# schema_v3_1.net
KiCad netlist of a schematic drawn in EAGLE
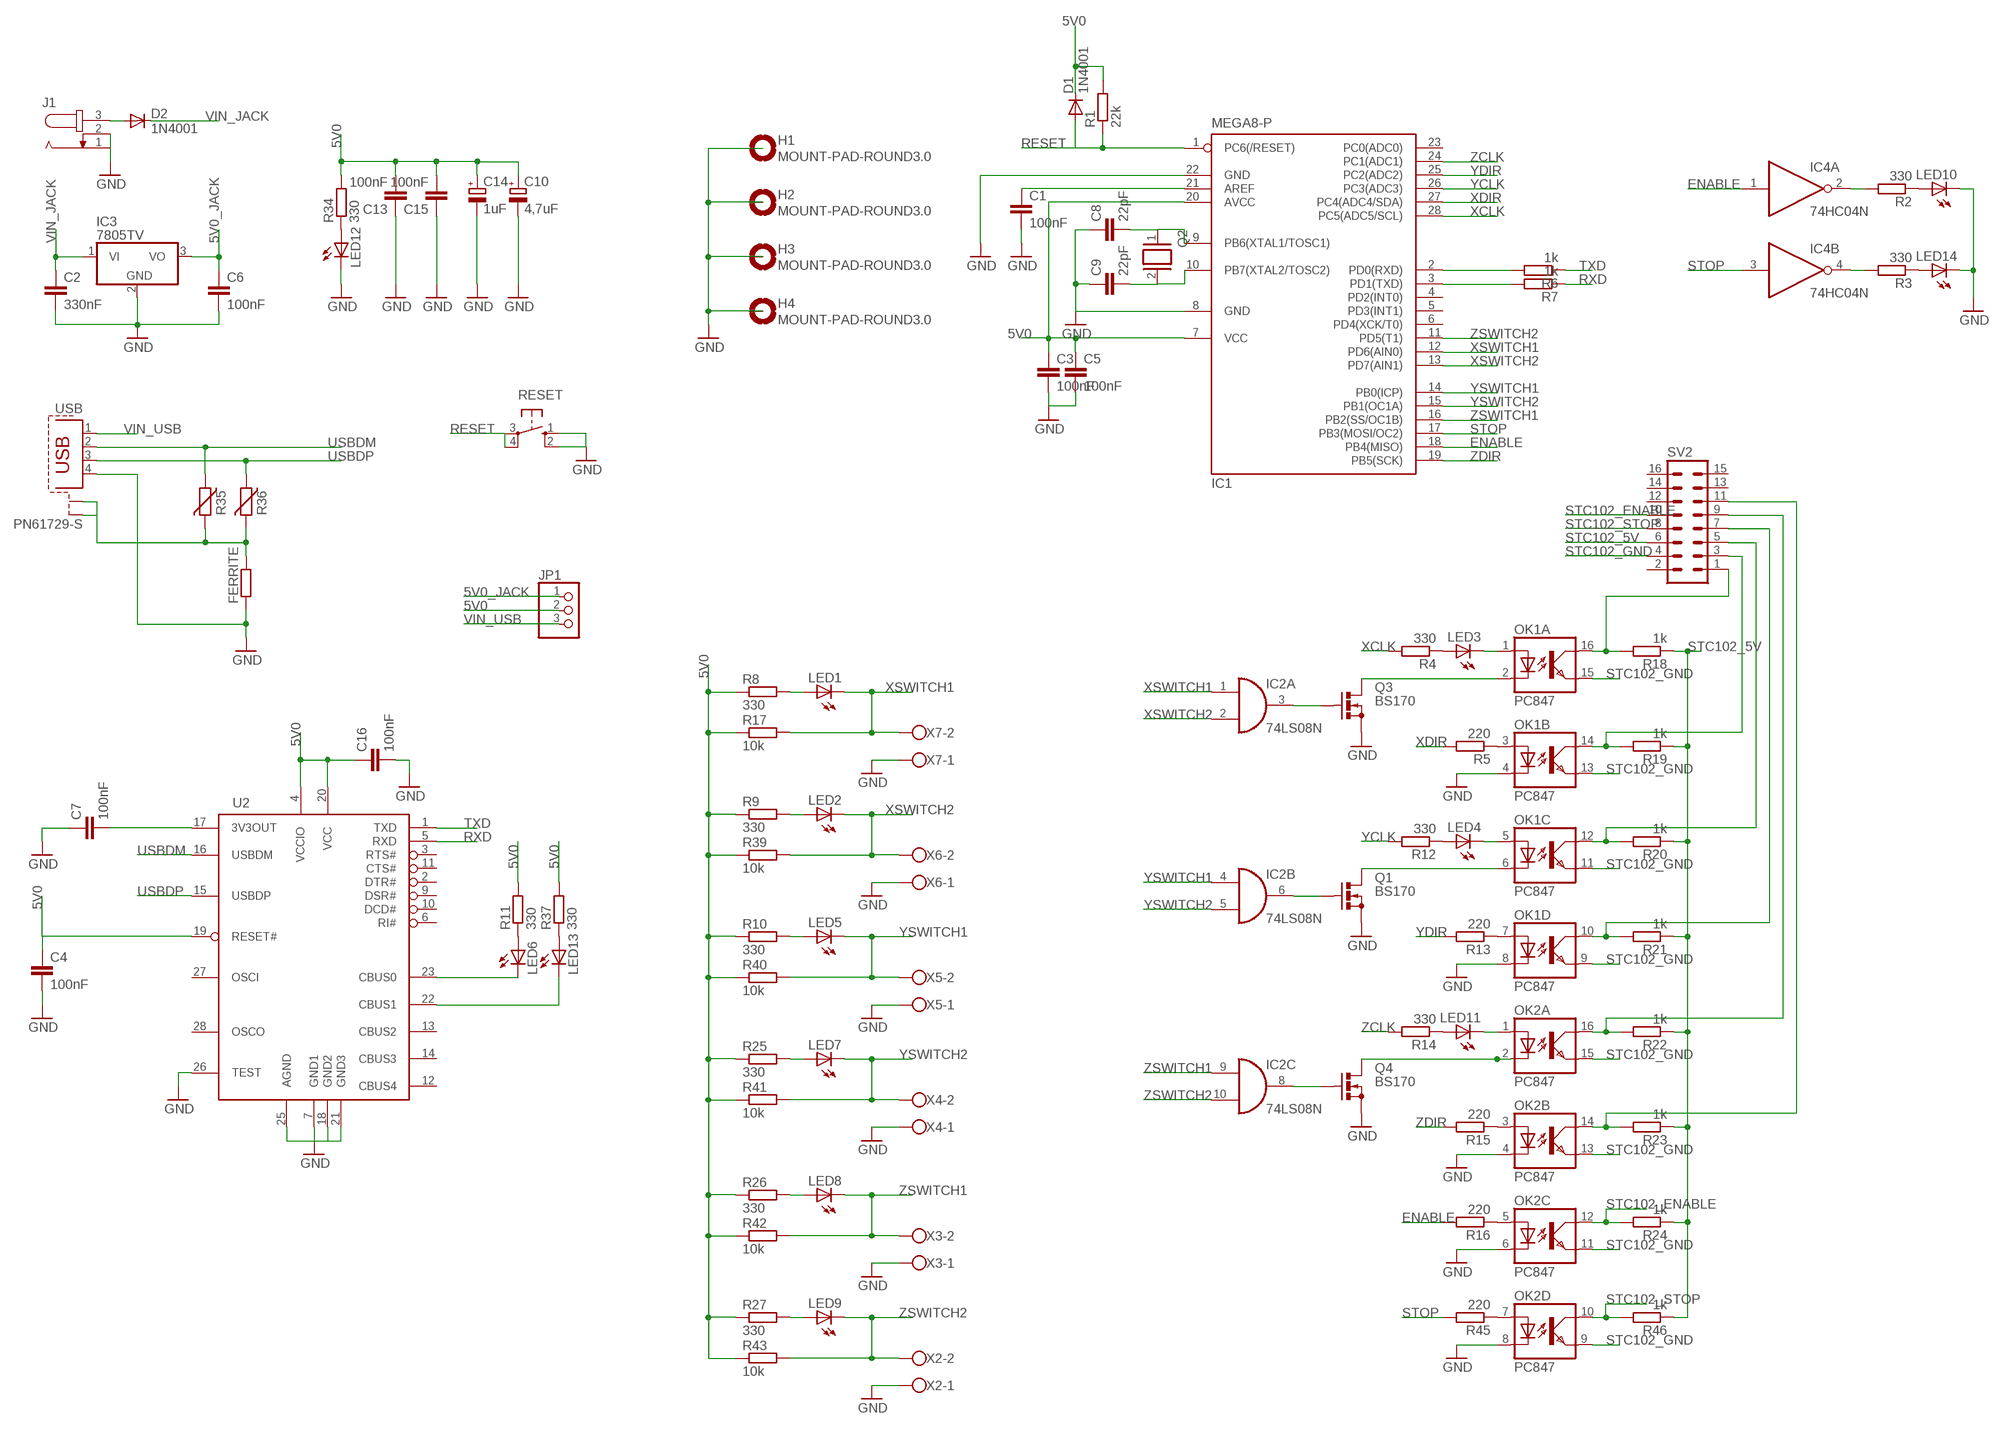
[diagram p0: schematic, sheet 1]

(export (version "E")
  (design (tool "Eeschema 10.0.6"))
  (components
    (comp (ref "C1")
      (value "100nF")
      (footprint "eagle-import:C0805")
      (libsource (lib "eagle-import") (part "C-EUC0805"))
    )
    (comp (ref "C2")
      (value "330nF")
      (footprint "eagle-import:C025-025X050")
      (libsource (lib "eagle-import") (part "C-EU025-025X050"))
    )
    (comp (ref "C3")
      (value "100nF")
      (footprint "eagle-import:C025-025X050")
      (libsource (lib "eagle-import") (part "C-EU025-025X050"))
    )
    (comp (ref "C4")
      (value "100nF")
      (footprint "eagle-import:C0603K")
      (libsource (lib "eagle-import") (part "C-EUC0603K"))
    )
    (comp (ref "C5")
      (value "100nF")
      (footprint "eagle-import:C025-025X050")
      (libsource (lib "eagle-import") (part "C-EU025-025X050"))
    )
    (comp (ref "C6")
      (value "100nF")
      (footprint "eagle-import:C025-025X050")
      (libsource (lib "eagle-import") (part "C-EU025-025X050"))
    )
    (comp (ref "C7")
      (value "100nF")
      (footprint "eagle-import:C0603K")
      (libsource (lib "eagle-import") (part "C-EUC0603K"))
    )
    (comp (ref "C8")
      (value "22pF")
      (footprint "eagle-import:C025-025X050")
      (libsource (lib "eagle-import") (part "C-EU025-025X050"))
    )
    (comp (ref "C9")
      (value "22pF")
      (footprint "eagle-import:C025-025X050")
      (libsource (lib "eagle-import") (part "C-EU025-025X050"))
    )
    (comp (ref "C10")
      (value "4,7uF")
      (footprint "eagle-import:E2,5-5")
      (libsource (lib "eagle-import") (part "CPOL-EUE2.5-5"))
    )
    (comp (ref "C13")
      (value "100nF")
      (footprint "eagle-import:C025-025X050")
      (libsource (lib "eagle-import") (part "C-EU025-025X050"))
    )
    (comp (ref "C14")
      (value "1uF")
      (footprint "eagle-import:E2,5-5")
      (libsource (lib "eagle-import") (part "CPOL-EUE2.5-5"))
    )
    (comp (ref "C15")
      (value "100nF")
      (footprint "eagle-import:C025-025X050")
      (libsource (lib "eagle-import") (part "C-EU025-025X050"))
    )
    (comp (ref "C16")
      (value "100nF")
      (footprint "eagle-import:C0603K")
      (libsource (lib "eagle-import") (part "C-EUC0603K"))
    )
    (comp (ref "D1")
      (value "1N4001")
      (footprint "eagle-import:DO41-10")
      (libsource (lib "eagle-import") (part "1N4004"))
    )
    (comp (ref "D2")
      (value "1N4001")
      (footprint "eagle-import:DO41-10")
      (libsource (lib "eagle-import") (part "1N4004"))
    )
    (comp (ref "FERRITE")
      (value "R-EU_M0805")
      (footprint "eagle-import:M0805")
      (libsource (lib "eagle-import") (part "resistor_R-EU_M0805"))
    )
    (comp (ref "H1")
      (value "MOUNT-PAD-ROUND3.0")
      (footprint "eagle-import:3,0-PAD")
      (libsource (lib "eagle-import") (part "MOUNT-PAD-ROUND3.0"))
    )
    (comp (ref "H2")
      (value "MOUNT-PAD-ROUND3.0")
      (footprint "eagle-import:3,0-PAD")
      (libsource (lib "eagle-import") (part "MOUNT-PAD-ROUND3.0"))
    )
    (comp (ref "H3")
      (value "MOUNT-PAD-ROUND3.0")
      (footprint "eagle-import:3,0-PAD")
      (libsource (lib "eagle-import") (part "MOUNT-PAD-ROUND3.0"))
    )
    (comp (ref "H4")
      (value "MOUNT-PAD-ROUND3.0")
      (footprint "eagle-import:3,0-PAD")
      (libsource (lib "eagle-import") (part "MOUNT-PAD-ROUND3.0"))
    )
    (comp (ref "IC1")
      (value "MEGA8-P")
      (footprint "eagle-import:DIL28-3")
      (libsource (lib "eagle-import") (part "MEGA8-P"))
    )
    (comp (ref "IC2")
      (value "74LS08N")
      (footprint "eagle-import:DIL14")
      (libsource (lib "eagle-import") (part "7408NLS"))
    )
    (comp (ref "IC3")
      (value "7805TV")
      (footprint "eagle-import:TO220V")
      (libsource (lib "eagle-import") (part "78TV05"))
    )
    (comp (ref "IC4")
      (value "74HC04N")
      (footprint "eagle-import:DIL14")
      (libsource (lib "eagle-import") (part "7404NHC"))
    )
    (comp (ref "J1")
      (value "JACK-PLUG0")
      (footprint "eagle-import:SPC4077")
      (libsource (lib "eagle-import") (part "JACK-PLUG0"))
    )
    (comp (ref "JP1")
      (value "PINHD-1X3")
      (footprint "eagle-import:1X03")
      (libsource (lib "eagle-import") (part "PINHD-1X3"))
    )
    (comp (ref "LED1")
      (value "LED3MM")
      (footprint "eagle-import:LED3MM")
      (libsource (lib "eagle-import") (part "LED3MM"))
    )
    (comp (ref "LED2")
      (value "LED3MM")
      (footprint "eagle-import:LED3MM")
      (libsource (lib "eagle-import") (part "LED3MM"))
    )
    (comp (ref "LED3")
      (value "LED3MM")
      (footprint "eagle-import:LED3MM")
      (libsource (lib "eagle-import") (part "LED3MM"))
    )
    (comp (ref "LED4")
      (value "LED3MM")
      (footprint "eagle-import:LED3MM")
      (libsource (lib "eagle-import") (part "LED3MM"))
    )
    (comp (ref "LED5")
      (value "LED3MM")
      (footprint "eagle-import:LED3MM")
      (libsource (lib "eagle-import") (part "LED3MM"))
    )
    (comp (ref "LED6")
      (value "LED3MM")
      (footprint "eagle-import:LED3MM")
      (libsource (lib "eagle-import") (part "LED3MM"))
    )
    (comp (ref "LED7")
      (value "LED3MM")
      (footprint "eagle-import:LED3MM")
      (libsource (lib "eagle-import") (part "LED3MM"))
    )
    (comp (ref "LED8")
      (value "LED3MM")
      (footprint "eagle-import:LED3MM")
      (libsource (lib "eagle-import") (part "LED3MM"))
    )
    (comp (ref "LED9")
      (value "LED3MM")
      (footprint "eagle-import:LED3MM")
      (libsource (lib "eagle-import") (part "LED3MM"))
    )
    (comp (ref "LED10")
      (value "LED3MM")
      (footprint "eagle-import:LED3MM")
      (libsource (lib "eagle-import") (part "LED3MM"))
    )
    (comp (ref "LED11")
      (value "LED3MM")
      (footprint "eagle-import:LED3MM")
      (libsource (lib "eagle-import") (part "LED3MM"))
    )
    (comp (ref "LED12")
      (value "LED3MM")
      (footprint "eagle-import:LED3MM")
      (libsource (lib "eagle-import") (part "LED3MM"))
    )
    (comp (ref "LED13")
      (value "LED3MM")
      (footprint "eagle-import:LED3MM")
      (libsource (lib "eagle-import") (part "LED3MM"))
    )
    (comp (ref "LED14")
      (value "LED3MM")
      (footprint "eagle-import:LED3MM")
      (libsource (lib "eagle-import") (part "LED3MM"))
    )
    (comp (ref "OK1")
      (value "PC847")
      (footprint "eagle-import:DIL16")
      (libsource (lib "eagle-import") (part "PC847"))
    )
    (comp (ref "OK2")
      (value "PC847")
      (footprint "eagle-import:DIL16")
      (libsource (lib "eagle-import") (part "PC847"))
    )
    (comp (ref "Q1")
      (value "BS170")
      (footprint "eagle-import:SOT54E")
      (libsource (lib "eagle-import") (part "BS170"))
    )
    (comp (ref "Q2")
      (value "XTAL/S")
      (footprint "eagle-import:QS")
      (libsource (lib "eagle-import") (part "XTAL/S"))
    )
    (comp (ref "Q3")
      (value "BS170")
      (footprint "eagle-import:SOT54E")
      (libsource (lib "eagle-import") (part "BS170"))
    )
    (comp (ref "Q4")
      (value "BS170")
      (footprint "eagle-import:SOT54E")
      (libsource (lib "eagle-import") (part "BS170"))
    )
    (comp (ref "R1")
      (value "22k")
      (footprint "eagle-import:0207_10")
      (libsource (lib "eagle-import") (part "R-EU_0207/10"))
    )
    (comp (ref "R2")
      (value "330")
      (footprint "eagle-import:0207_10")
      (libsource (lib "eagle-import") (part "R-EU_0207/10"))
    )
    (comp (ref "R3")
      (value "330")
      (footprint "eagle-import:0207_10")
      (libsource (lib "eagle-import") (part "R-EU_0207/10"))
    )
    (comp (ref "R4")
      (value "330")
      (footprint "eagle-import:0207_10")
      (libsource (lib "eagle-import") (part "R-EU_0207/10"))
    )
    (comp (ref "R5")
      (value "220")
      (footprint "eagle-import:0207_10")
      (libsource (lib "eagle-import") (part "R-EU_0207/10"))
    )
    (comp (ref "R6")
      (value "1k")
      (footprint "eagle-import:0207_10")
      (libsource (lib "eagle-import") (part "R-EU_0207/10"))
    )
    (comp (ref "R7")
      (value "1k")
      (footprint "eagle-import:0207_10")
      (libsource (lib "eagle-import") (part "R-EU_0207/10"))
    )
    (comp (ref "R8")
      (value "330")
      (footprint "eagle-import:0207_10")
      (libsource (lib "eagle-import") (part "R-EU_0207/10"))
    )
    (comp (ref "R9")
      (value "330")
      (footprint "eagle-import:0207_10")
      (libsource (lib "eagle-import") (part "R-EU_0207/10"))
    )
    (comp (ref "R10")
      (value "330")
      (footprint "eagle-import:0207_10")
      (libsource (lib "eagle-import") (part "R-EU_0207/10"))
    )
    (comp (ref "R11")
      (value "330")
      (footprint "eagle-import:0207_10")
      (libsource (lib "eagle-import") (part "R-EU_0207/10"))
    )
    (comp (ref "R12")
      (value "330")
      (footprint "eagle-import:0207_10")
      (libsource (lib "eagle-import") (part "R-EU_0207/10"))
    )
    (comp (ref "R13")
      (value "220")
      (footprint "eagle-import:0207_10")
      (libsource (lib "eagle-import") (part "R-EU_0207/10"))
    )
    (comp (ref "R14")
      (value "330")
      (footprint "eagle-import:0207_10")
      (libsource (lib "eagle-import") (part "R-EU_0207/10"))
    )
    (comp (ref "R15")
      (value "220")
      (footprint "eagle-import:0207_10")
      (libsource (lib "eagle-import") (part "R-EU_0207/10"))
    )
    (comp (ref "R16")
      (value "220")
      (footprint "eagle-import:0207_10")
      (libsource (lib "eagle-import") (part "R-EU_0207/10"))
    )
    (comp (ref "R17")
      (value "10k")
      (footprint "eagle-import:0207_10")
      (libsource (lib "eagle-import") (part "R-EU_0207/10"))
    )
    (comp (ref "R18")
      (value "1k")
      (footprint "eagle-import:0207_10")
      (libsource (lib "eagle-import") (part "R-EU_0207/10"))
    )
    (comp (ref "R19")
      (value "1k")
      (footprint "eagle-import:0207_10")
      (libsource (lib "eagle-import") (part "R-EU_0207/10"))
    )
    (comp (ref "R20")
      (value "1k")
      (footprint "eagle-import:0207_10")
      (libsource (lib "eagle-import") (part "R-EU_0207/10"))
    )
    (comp (ref "R21")
      (value "1k")
      (footprint "eagle-import:0207_10")
      (libsource (lib "eagle-import") (part "R-EU_0207/10"))
    )
    (comp (ref "R22")
      (value "1k")
      (footprint "eagle-import:0207_10")
      (libsource (lib "eagle-import") (part "R-EU_0207/10"))
    )
    (comp (ref "R23")
      (value "1k")
      (footprint "eagle-import:0207_10")
      (libsource (lib "eagle-import") (part "R-EU_0207/10"))
    )
    (comp (ref "R24")
      (value "1k")
      (footprint "eagle-import:0207_10")
      (libsource (lib "eagle-import") (part "R-EU_0207/10"))
    )
    (comp (ref "R25")
      (value "330")
      (footprint "eagle-import:0207_10")
      (libsource (lib "eagle-import") (part "R-EU_0207/10"))
    )
    (comp (ref "R26")
      (value "330")
      (footprint "eagle-import:0207_10")
      (libsource (lib "eagle-import") (part "R-EU_0207/10"))
    )
    (comp (ref "R27")
      (value "330")
      (footprint "eagle-import:0207_10")
      (libsource (lib "eagle-import") (part "R-EU_0207/10"))
    )
    (comp (ref "R34")
      (value "330")
      (footprint "eagle-import:0207_10")
      (libsource (lib "eagle-import") (part "R-EU_0207/10"))
    )
    (comp (ref "R35")
      (value "VARISTORCN0603")
      (footprint "eagle-import:CT_CN0603")
      (libsource (lib "eagle-import") (part "VARISTORCN0603"))
    )
    (comp (ref "R36")
      (value "VARISTORCN0603")
      (footprint "eagle-import:CT_CN0603")
      (libsource (lib "eagle-import") (part "VARISTORCN0603"))
    )
    (comp (ref "R37")
      (value "330")
      (footprint "eagle-import:0207_10")
      (libsource (lib "eagle-import") (part "R-EU_0207/10"))
    )
    (comp (ref "R39")
      (value "10k")
      (footprint "eagle-import:0207_10")
      (libsource (lib "eagle-import") (part "R-EU_0207/10"))
    )
    (comp (ref "R40")
      (value "10k")
      (footprint "eagle-import:0207_10")
      (libsource (lib "eagle-import") (part "R-EU_0207/10"))
    )
    (comp (ref "R41")
      (value "10k")
      (footprint "eagle-import:0207_10")
      (libsource (lib "eagle-import") (part "R-EU_0207/10"))
    )
    (comp (ref "R42")
      (value "10k")
      (footprint "eagle-import:0207_10")
      (libsource (lib "eagle-import") (part "R-EU_0207/10"))
    )
    (comp (ref "R43")
      (value "10k")
      (footprint "eagle-import:0207_10")
      (libsource (lib "eagle-import") (part "R-EU_0207/10"))
    )
    (comp (ref "R45")
      (value "220")
      (footprint "eagle-import:0207_10")
      (libsource (lib "eagle-import") (part "R-EU_0207/10"))
    )
    (comp (ref "R46")
      (value "1k")
      (footprint "eagle-import:0207_10")
      (libsource (lib "eagle-import") (part "R-EU_0207/10"))
    )
    (comp (ref "RESET")
      (value "10-XX")
      (footprint "eagle-import:B3F-10XX")
      (fields (field (name "MPN") "B3F-1000"))
      (libsource (lib "eagle-import") (part "10-XX"))
    )
    (comp (ref "SV2")
      (value "MA08-2")
      (footprint "eagle-import:MA08-2")
      (libsource (lib "eagle-import") (part "MA08-2"))
    )
    (comp (ref "U2")
      (value "FT232RL")
      (footprint "eagle-import:SSOP28DB")
      (libsource (lib "eagle-import") (part "FT232RL"))
    )
    (comp (ref "USB")
      (value "PN61729-S")
      (footprint "eagle-import:PN61729-S")
      (fields (field (name "OC_FARNELL") "unknown") (field (name "OC_NEWARK") "unknown"))
      (libsource (lib "eagle-import") (part "PN61729-S"))
    )
    (comp (ref "X2")
      (value "W237-102")
      (footprint "eagle-import:W237-102")
      (fields (field (name "MPN") "237-102"))
      (libsource (lib "eagle-import") (part "W237-102"))
    )
    (comp (ref "X3")
      (value "W237-102")
      (footprint "eagle-import:W237-102")
      (fields (field (name "MPN") "237-102"))
      (libsource (lib "eagle-import") (part "W237-102"))
    )
    (comp (ref "X4")
      (value "W237-102")
      (footprint "eagle-import:W237-102")
      (fields (field (name "MPN") "237-102"))
      (libsource (lib "eagle-import") (part "W237-102"))
    )
    (comp (ref "X5")
      (value "W237-102")
      (footprint "eagle-import:W237-102")
      (fields (field (name "MPN") "237-102"))
      (libsource (lib "eagle-import") (part "W237-102"))
    )
    (comp (ref "X6")
      (value "W237-102")
      (footprint "eagle-import:W237-102")
      (fields (field (name "MPN") "237-102"))
      (libsource (lib "eagle-import") (part "W237-102"))
    )
    (comp (ref "X7")
      (value "W237-102")
      (footprint "eagle-import:W237-102")
      (fields (field (name "MPN") "237-102"))
      (libsource (lib "eagle-import") (part "W237-102"))
    )
  )
  (nets
    (net (code "1") (name "/5V0") (class "Default")
      (node (ref "C10") (pin "+") (pinfunction "+_+") (pintype "passive"))
      (node (ref "C13") (pin "2") (pinfunction "2_2") (pintype "passive"))
      (node (ref "C14") (pin "+") (pinfunction "+_+") (pintype "passive"))
      (node (ref "C15") (pin "2") (pinfunction "2_2") (pintype "passive"))
      (node (ref "C16") (pin "1") (pinfunction "1_1") (pintype "passive"))
      (node (ref "C3") (pin "1") (pinfunction "1_1") (pintype "passive"))
      (node (ref "C4") (pin "1") (pinfunction "1_1") (pintype "passive"))
      (node (ref "C5") (pin "1") (pinfunction "1_1") (pintype "passive"))
      (node (ref "D1") (pin "C") (pinfunction "C_C") (pintype "passive"))
      (node (ref "IC1") (pin "20") (pinfunction "AVCC_20") (pintype "power_in"))
      (node (ref "IC1") (pin "7") (pinfunction "VCC_7") (pintype "power_in"))
      (node (ref "JP1") (pin "2") (pinfunction "2_2") (pintype "passive"))
      (node (ref "R1") (pin "2") (pinfunction "2_2") (pintype "passive"))
      (node (ref "R10") (pin "1") (pinfunction "1_1") (pintype "passive"))
      (node (ref "R11") (pin "2") (pinfunction "2_2") (pintype "passive"))
      (node (ref "R17") (pin "1") (pinfunction "1_1") (pintype "passive"))
      (node (ref "R25") (pin "1") (pinfunction "1_1") (pintype "passive"))
      (node (ref "R26") (pin "1") (pinfunction "1_1") (pintype "passive"))
      (node (ref "R27") (pin "1") (pinfunction "1_1") (pintype "passive"))
      (node (ref "R34") (pin "2") (pinfunction "2_2") (pintype "passive"))
      (node (ref "R37") (pin "2") (pinfunction "2_2") (pintype "passive"))
      (node (ref "R39") (pin "1") (pinfunction "1_1") (pintype "passive"))
      (node (ref "R40") (pin "1") (pinfunction "1_1") (pintype "passive"))
      (node (ref "R41") (pin "1") (pinfunction "1_1") (pintype "passive"))
      (node (ref "R42") (pin "1") (pinfunction "1_1") (pintype "passive"))
      (node (ref "R43") (pin "1") (pinfunction "1_1") (pintype "passive"))
      (node (ref "R8") (pin "1") (pinfunction "1_1") (pintype "passive"))
      (node (ref "R9") (pin "1") (pinfunction "1_1") (pintype "passive"))
      (node (ref "U2") (pin "19") (pinfunction "RESET#_19") (pintype "input"))
      (node (ref "U2") (pin "20") (pinfunction "VCC_20") (pintype "power_in"))
      (node (ref "U2") (pin "4") (pinfunction "VCCIO_4") (pintype "power_in"))
    )
    (net (code "2") (name "/5V0_JACK") (class "Default")
      (node (ref "C6") (pin "1") (pinfunction "1_1") (pintype "passive"))
      (node (ref "IC3") (pin "3") (pinfunction "VO_3") (pintype "passive"))
      (node (ref "JP1") (pin "1") (pinfunction "1_1") (pintype "passive"))
    )
    (net (code "3") (name "/ENABLE") (class "Default")
      (node (ref "IC1") (pin "18") (pinfunction "PB4(MISO)_18") (pintype "bidirectional"))
      (node (ref "IC4") (pin "1") (pinfunction "I_1") (pintype "input"))
      (node (ref "R16") (pin "2") (pinfunction "2_2") (pintype "passive"))
    )
    (net (code "4") (name "/RESET") (class "Default")
      (node (ref "D1") (pin "A") (pinfunction "A_A") (pintype "passive"))
      (node (ref "IC1") (pin "1") (pinfunction "PC6(/RESET)_1") (pintype "bidirectional"))
      (node (ref "R1") (pin "1") (pinfunction "1_1") (pintype "passive"))
      (node (ref "RESET") (pin "3") (pinfunction "P_3") (pintype "passive"))
      (node (ref "RESET") (pin "4") (pinfunction "P1_4") (pintype "passive"))
    )
    (net (code "5") (name "/RXD") (class "Default")
      (node (ref "R7") (pin "1") (pinfunction "1_1") (pintype "passive"))
      (node (ref "U2") (pin "5") (pinfunction "RXD_5") (pintype "input"))
    )
    (net (code "6") (name "/STC102_5V") (class "Default")
      (node (ref "R18") (pin "1") (pinfunction "1_1") (pintype "passive"))
      (node (ref "R19") (pin "1") (pinfunction "1_1") (pintype "passive"))
      (node (ref "R20") (pin "1") (pinfunction "1_1") (pintype "passive"))
      (node (ref "R21") (pin "1") (pinfunction "1_1") (pintype "passive"))
      (node (ref "R22") (pin "1") (pinfunction "1_1") (pintype "passive"))
      (node (ref "R23") (pin "1") (pinfunction "1_1") (pintype "passive"))
      (node (ref "R24") (pin "1") (pinfunction "1_1") (pintype "passive"))
      (node (ref "R46") (pin "1") (pinfunction "1_1") (pintype "passive"))
      (node (ref "SV2") (pin "6") (pinfunction "6_6") (pintype "passive"))
    )
    (net (code "7") (name "/STC102_ENABLE") (class "Default")
      (node (ref "OK2") (pin "12") (pinfunction "COL_12") (pintype "passive"))
      (node (ref "R24") (pin "2") (pinfunction "2_2") (pintype "passive"))
      (node (ref "SV2") (pin "10") (pinfunction "10_10") (pintype "passive"))
    )
    (net (code "8") (name "/STC102_GND") (class "Default")
      (node (ref "OK1") (pin "11") (pinfunction "EMIT_11") (pintype "passive"))
      (node (ref "OK1") (pin "13") (pinfunction "EMIT_13") (pintype "passive"))
      (node (ref "OK1") (pin "15") (pinfunction "EMIT_15") (pintype "passive"))
      (node (ref "OK1") (pin "9") (pinfunction "EMIT_9") (pintype "passive"))
      (node (ref "OK2") (pin "11") (pinfunction "EMIT_11") (pintype "passive"))
      (node (ref "OK2") (pin "13") (pinfunction "EMIT_13") (pintype "passive"))
      (node (ref "OK2") (pin "15") (pinfunction "EMIT_15") (pintype "passive"))
      (node (ref "OK2") (pin "9") (pinfunction "EMIT_9") (pintype "passive"))
      (node (ref "SV2") (pin "4") (pinfunction "4_4") (pintype "passive"))
    )
    (net (code "9") (name "/STC102_STOP") (class "Default")
      (node (ref "OK2") (pin "10") (pinfunction "COL_10") (pintype "passive"))
      (node (ref "R46") (pin "2") (pinfunction "2_2") (pintype "passive"))
      (node (ref "SV2") (pin "8") (pinfunction "8_8") (pintype "passive"))
    )
    (net (code "10") (name "/STOP") (class "Default")
      (node (ref "IC1") (pin "17") (pinfunction "PB3(MOSI/OC2)_17") (pintype "bidirectional"))
      (node (ref "IC4") (pin "3") (pinfunction "I_3") (pintype "input"))
      (node (ref "R45") (pin "2") (pinfunction "2_2") (pintype "passive"))
    )
    (net (code "11") (name "/TXD") (class "Default")
      (node (ref "R6") (pin "1") (pinfunction "1_1") (pintype "passive"))
      (node (ref "U2") (pin "1") (pinfunction "TXD_1") (pintype "output"))
    )
    (net (code "12") (name "/USBDM") (class "Default")
      (node (ref "R35") (pin "1") (pinfunction "1_1") (pintype "passive"))
      (node (ref "U2") (pin "16") (pinfunction "USBDM_16") (pintype "bidirectional"))
      (node (ref "USB") (pin "2") (pinfunction "2_2") (pintype "passive"))
    )
    (net (code "13") (name "/USBDP") (class "Default")
      (node (ref "R36") (pin "1") (pinfunction "1_1") (pintype "passive"))
      (node (ref "U2") (pin "15") (pinfunction "USBDP_15") (pintype "bidirectional"))
      (node (ref "USB") (pin "3") (pinfunction "3_3") (pintype "passive"))
    )
    (net (code "14") (name "/VIN_JACK") (class "Default")
      (node (ref "C2") (pin "1") (pinfunction "1_1") (pintype "passive"))
      (node (ref "D2") (pin "C") (pinfunction "C_C") (pintype "passive"))
      (node (ref "IC3") (pin "1") (pinfunction "VI_1") (pintype "input"))
    )
    (net (code "15") (name "/VIN_USB") (class "Default")
      (node (ref "JP1") (pin "3") (pinfunction "3_3") (pintype "passive"))
      (node (ref "USB") (pin "1") (pinfunction "1_1") (pintype "passive"))
    )
    (net (code "16") (name "/XCLK") (class "Default")
      (node (ref "IC1") (pin "28") (pinfunction "PC5(ADC5/SCL)_28") (pintype "bidirectional"))
      (node (ref "R4") (pin "2") (pinfunction "2_2") (pintype "passive"))
    )
    (net (code "17") (name "/XDIR") (class "Default")
      (node (ref "IC1") (pin "27") (pinfunction "PC4(ADC4/SDA)_27") (pintype "bidirectional"))
      (node (ref "R5") (pin "2") (pinfunction "2_2") (pintype "passive"))
    )
    (net (code "18") (name "/XSWITCH1") (class "Default")
      (node (ref "IC1") (pin "12") (pinfunction "PD6(AIN0)_12") (pintype "bidirectional"))
      (node (ref "IC2") (pin "1") (pinfunction "I0_1") (pintype "input"))
      (node (ref "LED1") (pin "K") (pinfunction "C_K") (pintype "passive"))
      (node (ref "R17") (pin "2") (pinfunction "2_2") (pintype "passive"))
      (node (ref "X7") (pin "2") (pinfunction "KL_2") (pintype "passive"))
    )
    (net (code "19") (name "/XSWITCH2") (class "Default")
      (node (ref "IC1") (pin "13") (pinfunction "PD7(AIN1)_13") (pintype "bidirectional"))
      (node (ref "IC2") (pin "2") (pinfunction "I1_2") (pintype "input"))
      (node (ref "LED2") (pin "K") (pinfunction "C_K") (pintype "passive"))
      (node (ref "R39") (pin "2") (pinfunction "2_2") (pintype "passive"))
      (node (ref "X6") (pin "2") (pinfunction "KL_2") (pintype "passive"))
    )
    (net (code "20") (name "/YCLK") (class "Default")
      (node (ref "IC1") (pin "26") (pinfunction "PC3(ADC3)_26") (pintype "bidirectional"))
      (node (ref "R12") (pin "2") (pinfunction "2_2") (pintype "passive"))
    )
    (net (code "21") (name "/YDIR") (class "Default")
      (node (ref "IC1") (pin "25") (pinfunction "PC2(ADC2)_25") (pintype "bidirectional"))
      (node (ref "R13") (pin "2") (pinfunction "2_2") (pintype "passive"))
    )
    (net (code "22") (name "/YSWITCH1") (class "Default")
      (node (ref "IC1") (pin "14") (pinfunction "PB0(ICP)_14") (pintype "bidirectional"))
      (node (ref "IC2") (pin "4") (pinfunction "I0_4") (pintype "input"))
      (node (ref "LED5") (pin "K") (pinfunction "C_K") (pintype "passive"))
      (node (ref "R40") (pin "2") (pinfunction "2_2") (pintype "passive"))
      (node (ref "X5") (pin "2") (pinfunction "KL_2") (pintype "passive"))
    )
    (net (code "23") (name "/YSWITCH2") (class "Default")
      (node (ref "IC1") (pin "15") (pinfunction "PB1(OC1A)_15") (pintype "bidirectional"))
      (node (ref "IC2") (pin "5") (pinfunction "I1_5") (pintype "input"))
      (node (ref "LED7") (pin "K") (pinfunction "C_K") (pintype "passive"))
      (node (ref "R41") (pin "2") (pinfunction "2_2") (pintype "passive"))
      (node (ref "X4") (pin "2") (pinfunction "KL_2") (pintype "passive"))
    )
    (net (code "24") (name "/ZCLK") (class "Default")
      (node (ref "IC1") (pin "24") (pinfunction "PC1(ADC1)_24") (pintype "bidirectional"))
      (node (ref "R14") (pin "2") (pinfunction "2_2") (pintype "passive"))
    )
    (net (code "25") (name "/ZDIR") (class "Default")
      (node (ref "IC1") (pin "19") (pinfunction "PB5(SCK)_19") (pintype "bidirectional"))
      (node (ref "R15") (pin "2") (pinfunction "2_2") (pintype "passive"))
    )
    (net (code "26") (name "/ZSWITCH1") (class "Default")
      (node (ref "IC1") (pin "16") (pinfunction "PB2(SS/OC1B)_16") (pintype "bidirectional"))
      (node (ref "IC2") (pin "9") (pinfunction "I0_9") (pintype "input"))
      (node (ref "LED8") (pin "K") (pinfunction "C_K") (pintype "passive"))
      (node (ref "R42") (pin "2") (pinfunction "2_2") (pintype "passive"))
      (node (ref "X3") (pin "2") (pinfunction "KL_2") (pintype "passive"))
    )
    (net (code "27") (name "/ZSWITCH2") (class "Default")
      (node (ref "IC1") (pin "11") (pinfunction "PD5(T1)_11") (pintype "bidirectional"))
      (node (ref "IC2") (pin "10") (pinfunction "I1_10") (pintype "input"))
      (node (ref "LED9") (pin "K") (pinfunction "C_K") (pintype "passive"))
      (node (ref "R43") (pin "2") (pinfunction "2_2") (pintype "passive"))
      (node (ref "X2") (pin "2") (pinfunction "KL_2") (pintype "passive"))
    )
    (net (code "28") (name "GND") (class "Default")
      (node (ref "C1") (pin "2") (pinfunction "2_2") (pintype "passive"))
      (node (ref "C10") (pin "-") (pinfunction "-_-") (pintype "passive"))
      (node (ref "C13") (pin "1") (pinfunction "1_1") (pintype "passive"))
      (node (ref "C14") (pin "-") (pinfunction "-_-") (pintype "passive"))
      (node (ref "C15") (pin "1") (pinfunction "1_1") (pintype "passive"))
      (node (ref "C16") (pin "2") (pinfunction "2_2") (pintype "passive"))
      (node (ref "C2") (pin "2") (pinfunction "2_2") (pintype "passive"))
      (node (ref "C3") (pin "2") (pinfunction "2_2") (pintype "passive"))
      (node (ref "C4") (pin "2") (pinfunction "2_2") (pintype "passive"))
      (node (ref "C5") (pin "2") (pinfunction "2_2") (pintype "passive"))
      (node (ref "C6") (pin "2") (pinfunction "2_2") (pintype "passive"))
      (node (ref "C7") (pin "1") (pinfunction "1_1") (pintype "passive"))
      (node (ref "C8") (pin "1") (pinfunction "1_1") (pintype "passive"))
      (node (ref "C9") (pin "1") (pinfunction "1_1") (pintype "passive"))
      (node (ref "FERRITE") (pin "1") (pinfunction "1_1") (pintype "passive"))
      (node (ref "IC1") (pin "22") (pinfunction "GND_22") (pintype "power_in"))
      (node (ref "IC1") (pin "8") (pinfunction "GND_8") (pintype "power_in"))
      (node (ref "IC3") (pin "2") (pinfunction "GND_2") (pintype "passive"))
      (node (ref "J1") (pin "1") (pinfunction "1_1") (pintype "passive"))
      (node (ref "J1") (pin "2") (pinfunction "2_2") (pintype "passive"))
      (node (ref "LED10") (pin "K") (pinfunction "C_K") (pintype "passive"))
      (node (ref "LED12") (pin "K") (pinfunction "C_K") (pintype "passive"))
      (node (ref "LED14") (pin "K") (pinfunction "C_K") (pintype "passive"))
      (node (ref "OK1") (pin "4") (pinfunction "C_4") (pintype "passive"))
      (node (ref "OK1") (pin "8") (pinfunction "C_8") (pintype "passive"))
      (node (ref "OK2") (pin "4") (pinfunction "C_4") (pintype "passive"))
      (node (ref "OK2") (pin "6") (pinfunction "C_6") (pintype "passive"))
      (node (ref "OK2") (pin "8") (pinfunction "C_8") (pintype "passive"))
      (node (ref "Q1") (pin "S") (pinfunction "S_S") (pintype "passive"))
      (node (ref "Q3") (pin "S") (pinfunction "S_S") (pintype "passive"))
      (node (ref "Q4") (pin "S") (pinfunction "S_S") (pintype "passive"))
      (node (ref "RESET") (pin "1") (pinfunction "S_1") (pintype "passive"))
      (node (ref "RESET") (pin "2") (pinfunction "S1_2") (pintype "passive"))
      (node (ref "U2") (pin "18") (pinfunction "GND2_18") (pintype "power_in"))
      (node (ref "U2") (pin "21") (pinfunction "GND3_21") (pintype "power_in"))
      (node (ref "U2") (pin "25") (pinfunction "AGND_25") (pintype "power_in"))
      (node (ref "U2") (pin "26") (pinfunction "TEST_26") (pintype "input"))
      (node (ref "U2") (pin "7") (pinfunction "GND1_7") (pintype "power_in"))
      (node (ref "USB") (pin "4") (pinfunction "4_4") (pintype "passive"))
      (node (ref "X2") (pin "1") (pinfunction "KL_1") (pintype "passive"))
      (node (ref "X3") (pin "1") (pinfunction "KL_1") (pintype "passive"))
      (node (ref "X4") (pin "1") (pinfunction "KL_1") (pintype "passive"))
      (node (ref "X5") (pin "1") (pinfunction "KL_1") (pintype "passive"))
      (node (ref "X6") (pin "1") (pinfunction "KL_1") (pintype "passive"))
      (node (ref "X7") (pin "1") (pinfunction "KL_1") (pintype "passive"))
    )
    (net (code "29") (name "Net-(D2-PadA)") (class "Default")
      (node (ref "D2") (pin "A") (pinfunction "A_A") (pintype "passive"))
      (node (ref "J1") (pin "3") (pinfunction "3_3") (pintype "passive"))
    )
    (net (code "30") (name "Net-(FERRITE-Pad2)") (class "Default")
      (node (ref "FERRITE") (pin "2") (pinfunction "2_2") (pintype "passive"))
      (node (ref "R35") (pin "2") (pinfunction "2_2") (pintype "passive"))
      (node (ref "R36") (pin "2") (pinfunction "2_2") (pintype "passive"))
      (node (ref "USB") (pin "S1") (pinfunction "S1_S1") (pintype "passive"))
      (node (ref "USB") (pin "S2") (pinfunction "S2_S2") (pintype "passive"))
    )
    (net (code "31") (name "Net-(IC1-AREF)") (class "Default")
      (node (ref "C1") (pin "1") (pinfunction "1_1") (pintype "passive"))
      (node (ref "IC1") (pin "21") (pinfunction "AREF_21") (pintype "passive"))
    )
    (net (code "32") (name "Net-(IC1-PB6(XTAL1{slash}TOSC1))") (class "Default")
      (node (ref "C8") (pin "2") (pinfunction "2_2") (pintype "passive"))
      (node (ref "IC1") (pin "9") (pinfunction "PB6(XTAL1/TOSC1)_9") (pintype "bidirectional"))
      (node (ref "Q2") (pin "1") (pinfunction "1_1") (pintype "passive"))
    )
    (net (code "33") (name "Net-(IC1-PB7(XTAL2{slash}TOSC2))") (class "Default")
      (node (ref "C9") (pin "2") (pinfunction "2_2") (pintype "passive"))
      (node (ref "IC1") (pin "10") (pinfunction "PB7(XTAL2/TOSC2)_10") (pintype "bidirectional"))
      (node (ref "Q2") (pin "2") (pinfunction "2_2") (pintype "passive"))
    )
    (net (code "34") (name "Net-(IC1-PD0(RXD))") (class "Default")
      (node (ref "IC1") (pin "2") (pinfunction "PD0(RXD)_2") (pintype "bidirectional"))
      (node (ref "R6") (pin "2") (pinfunction "2_2") (pintype "passive"))
    )
    (net (code "35") (name "Net-(IC1-PD1(TXD))") (class "Default")
      (node (ref "IC1") (pin "3") (pinfunction "PD1(TXD)_3") (pintype "bidirectional"))
      (node (ref "R7") (pin "2") (pinfunction "2_2") (pintype "passive"))
    )
    (net (code "36") (name "Net-(IC2A-O)") (class "Default")
      (node (ref "IC2") (pin "3") (pinfunction "O_3") (pintype "output"))
      (node (ref "Q3") (pin "G") (pinfunction "G_G") (pintype "passive"))
    )
    (net (code "37") (name "Net-(IC2B-O)") (class "Default")
      (node (ref "IC2") (pin "6") (pinfunction "O_6") (pintype "output"))
      (node (ref "Q1") (pin "G") (pinfunction "G_G") (pintype "passive"))
    )
    (net (code "38") (name "Net-(IC2C-O)") (class "Default")
      (node (ref "IC2") (pin "8") (pinfunction "O_8") (pintype "output"))
      (node (ref "Q4") (pin "G") (pinfunction "G_G") (pintype "passive"))
    )
    (net (code "39") (name "Net-(IC4A-O)") (class "Default")
      (node (ref "IC4") (pin "2") (pinfunction "O_2") (pintype "output"))
      (node (ref "R2") (pin "2") (pinfunction "2_2") (pintype "passive"))
    )
    (net (code "40") (name "Net-(IC4B-O)") (class "Default")
      (node (ref "IC4") (pin "4") (pinfunction "O_4") (pintype "output"))
      (node (ref "R3") (pin "2") (pinfunction "2_2") (pintype "passive"))
    )
    (net (code "41") (name "Net-(LED1-PadA)") (class "Default")
      (node (ref "LED1") (pin "A") (pinfunction "A_A") (pintype "passive"))
      (node (ref "R8") (pin "2") (pinfunction "2_2") (pintype "passive"))
    )
    (net (code "42") (name "Net-(LED2-PadA)") (class "Default")
      (node (ref "LED2") (pin "A") (pinfunction "A_A") (pintype "passive"))
      (node (ref "R9") (pin "2") (pinfunction "2_2") (pintype "passive"))
    )
    (net (code "43") (name "Net-(LED3-C)") (class "Default")
      (node (ref "LED3") (pin "K") (pinfunction "C_K") (pintype "passive"))
      (node (ref "OK1") (pin "1") (pinfunction "A_1") (pintype "passive"))
    )
    (net (code "44") (name "Net-(LED3-PadA)") (class "Default")
      (node (ref "LED3") (pin "A") (pinfunction "A_A") (pintype "passive"))
      (node (ref "R4") (pin "1") (pinfunction "1_1") (pintype "passive"))
    )
    (net (code "45") (name "Net-(LED4-C)") (class "Default")
      (node (ref "LED4") (pin "K") (pinfunction "C_K") (pintype "passive"))
      (node (ref "OK1") (pin "5") (pinfunction "A_5") (pintype "passive"))
    )
    (net (code "46") (name "Net-(LED4-PadA)") (class "Default")
      (node (ref "LED4") (pin "A") (pinfunction "A_A") (pintype "passive"))
      (node (ref "R12") (pin "1") (pinfunction "1_1") (pintype "passive"))
    )
    (net (code "47") (name "Net-(LED5-PadA)") (class "Default")
      (node (ref "LED5") (pin "A") (pinfunction "A_A") (pintype "passive"))
      (node (ref "R10") (pin "2") (pinfunction "2_2") (pintype "passive"))
    )
    (net (code "48") (name "Net-(LED6-C)") (class "Default")
      (node (ref "LED6") (pin "K") (pinfunction "C_K") (pintype "passive"))
      (node (ref "U2") (pin "23") (pinfunction "CBUS0_23") (pintype "bidirectional"))
    )
    (net (code "49") (name "Net-(LED6-PadA)") (class "Default")
      (node (ref "LED6") (pin "A") (pinfunction "A_A") (pintype "passive"))
      (node (ref "R11") (pin "1") (pinfunction "1_1") (pintype "passive"))
    )
    (net (code "50") (name "Net-(LED7-PadA)") (class "Default")
      (node (ref "LED7") (pin "A") (pinfunction "A_A") (pintype "passive"))
      (node (ref "R25") (pin "2") (pinfunction "2_2") (pintype "passive"))
    )
    (net (code "51") (name "Net-(LED8-PadA)") (class "Default")
      (node (ref "LED8") (pin "A") (pinfunction "A_A") (pintype "passive"))
      (node (ref "R26") (pin "2") (pinfunction "2_2") (pintype "passive"))
    )
    (net (code "52") (name "Net-(LED9-PadA)") (class "Default")
      (node (ref "LED9") (pin "A") (pinfunction "A_A") (pintype "passive"))
      (node (ref "R27") (pin "2") (pinfunction "2_2") (pintype "passive"))
    )
    (net (code "53") (name "Net-(LED10-PadA)") (class "Default")
      (node (ref "LED10") (pin "A") (pinfunction "A_A") (pintype "passive"))
      (node (ref "R2") (pin "1") (pinfunction "1_1") (pintype "passive"))
    )
    (net (code "54") (name "Net-(LED11-C)") (class "Default")
      (node (ref "LED11") (pin "K") (pinfunction "C_K") (pintype "passive"))
      (node (ref "OK2") (pin "1") (pinfunction "A_1") (pintype "passive"))
    )
    (net (code "55") (name "Net-(LED11-PadA)") (class "Default")
      (node (ref "LED11") (pin "A") (pinfunction "A_A") (pintype "passive"))
      (node (ref "R14") (pin "1") (pinfunction "1_1") (pintype "passive"))
    )
    (net (code "56") (name "Net-(LED12-PadA)") (class "Default")
      (node (ref "LED12") (pin "A") (pinfunction "A_A") (pintype "passive"))
      (node (ref "R34") (pin "1") (pinfunction "1_1") (pintype "passive"))
    )
    (net (code "57") (name "Net-(LED13-C)") (class "Default")
      (node (ref "LED13") (pin "K") (pinfunction "C_K") (pintype "passive"))
      (node (ref "U2") (pin "22") (pinfunction "CBUS1_22") (pintype "bidirectional"))
    )
    (net (code "58") (name "Net-(LED13-PadA)") (class "Default")
      (node (ref "LED13") (pin "A") (pinfunction "A_A") (pintype "passive"))
      (node (ref "R37") (pin "1") (pinfunction "1_1") (pintype "passive"))
    )
    (net (code "59") (name "Net-(LED14-PadA)") (class "Default")
      (node (ref "LED14") (pin "A") (pinfunction "A_A") (pintype "passive"))
      (node (ref "R3") (pin "1") (pinfunction "1_1") (pintype "passive"))
    )
    (net (code "60") (name "Net-(OK1A-C)") (class "Default")
      (node (ref "OK1") (pin "2") (pinfunction "C_2") (pintype "passive"))
      (node (ref "Q3") (pin "D") (pinfunction "D_D") (pintype "passive"))
    )
    (net (code "61") (name "Net-(OK1A-COL)") (class "Default")
      (node (ref "OK1") (pin "16") (pinfunction "COL_16") (pintype "passive"))
      (node (ref "R18") (pin "2") (pinfunction "2_2") (pintype "passive"))
      (node (ref "SV2") (pin "1") (pinfunction "1_1") (pintype "passive"))
    )
    (net (code "62") (name "Net-(OK1B-A)") (class "Default")
      (node (ref "OK1") (pin "3") (pinfunction "A_3") (pintype "passive"))
      (node (ref "R5") (pin "1") (pinfunction "1_1") (pintype "passive"))
    )
    (net (code "63") (name "Net-(OK1B-COL)") (class "Default")
      (node (ref "OK1") (pin "14") (pinfunction "COL_14") (pintype "passive"))
      (node (ref "R19") (pin "2") (pinfunction "2_2") (pintype "passive"))
      (node (ref "SV2") (pin "3") (pinfunction "3_3") (pintype "passive"))
    )
    (net (code "64") (name "Net-(OK1C-C)") (class "Default")
      (node (ref "OK1") (pin "6") (pinfunction "C_6") (pintype "passive"))
      (node (ref "Q1") (pin "D") (pinfunction "D_D") (pintype "passive"))
    )
    (net (code "65") (name "Net-(OK1C-COL)") (class "Default")
      (node (ref "OK1") (pin "12") (pinfunction "COL_12") (pintype "passive"))
      (node (ref "R20") (pin "2") (pinfunction "2_2") (pintype "passive"))
      (node (ref "SV2") (pin "5") (pinfunction "5_5") (pintype "passive"))
    )
    (net (code "66") (name "Net-(OK1D-A)") (class "Default")
      (node (ref "OK1") (pin "7") (pinfunction "A_7") (pintype "passive"))
      (node (ref "R13") (pin "1") (pinfunction "1_1") (pintype "passive"))
    )
    (net (code "67") (name "Net-(OK1D-COL)") (class "Default")
      (node (ref "OK1") (pin "10") (pinfunction "COL_10") (pintype "passive"))
      (node (ref "R21") (pin "2") (pinfunction "2_2") (pintype "passive"))
      (node (ref "SV2") (pin "7") (pinfunction "7_7") (pintype "passive"))
    )
    (net (code "68") (name "Net-(OK2A-C)") (class "Default")
      (node (ref "OK2") (pin "2") (pinfunction "C_2") (pintype "passive"))
      (node (ref "Q4") (pin "D") (pinfunction "D_D") (pintype "passive"))
    )
    (net (code "69") (name "Net-(OK2A-COL)") (class "Default")
      (node (ref "OK2") (pin "16") (pinfunction "COL_16") (pintype "passive"))
      (node (ref "R22") (pin "2") (pinfunction "2_2") (pintype "passive"))
      (node (ref "SV2") (pin "9") (pinfunction "9_9") (pintype "passive"))
    )
    (net (code "70") (name "Net-(OK2B-A)") (class "Default")
      (node (ref "OK2") (pin "3") (pinfunction "A_3") (pintype "passive"))
      (node (ref "R15") (pin "1") (pinfunction "1_1") (pintype "passive"))
    )
    (net (code "71") (name "Net-(OK2B-COL)") (class "Default")
      (node (ref "OK2") (pin "14") (pinfunction "COL_14") (pintype "passive"))
      (node (ref "R23") (pin "2") (pinfunction "2_2") (pintype "passive"))
      (node (ref "SV2") (pin "11") (pinfunction "11_11") (pintype "passive"))
    )
    (net (code "72") (name "Net-(OK2C-A)") (class "Default")
      (node (ref "OK2") (pin "5") (pinfunction "A_5") (pintype "passive"))
      (node (ref "R16") (pin "1") (pinfunction "1_1") (pintype "passive"))
    )
    (net (code "73") (name "Net-(OK2D-A)") (class "Default")
      (node (ref "OK2") (pin "7") (pinfunction "A_7") (pintype "passive"))
      (node (ref "R45") (pin "1") (pinfunction "1_1") (pintype "passive"))
    )
    (net (code "74") (name "Net-(U2-3V3OUT)") (class "Default")
      (node (ref "C7") (pin "2") (pinfunction "2_2") (pintype "passive"))
      (node (ref "U2") (pin "17") (pinfunction "3V3OUT_17") (pintype "output"))
    )
    (net (code "75") (name "unconnected-(H1-MOUNT-PadB3,0)") (class "Default")
      (node (ref "H1") (pin "B3,0") (pinfunction "MOUNT_B3,0") (pintype "passive"))
    )
    (net (code "76") (name "unconnected-(H2-MOUNT-PadB3,0)") (class "Default")
      (node (ref "H2") (pin "B3,0") (pinfunction "MOUNT_B3,0") (pintype "passive"))
    )
    (net (code "77") (name "unconnected-(H3-MOUNT-PadB3,0)") (class "Default")
      (node (ref "H3") (pin "B3,0") (pinfunction "MOUNT_B3,0") (pintype "passive"))
    )
    (net (code "78") (name "unconnected-(H4-MOUNT-PadB3,0)") (class "Default")
      (node (ref "H4") (pin "B3,0") (pinfunction "MOUNT_B3,0") (pintype "passive"))
    )
    (net (code "79") (name "unconnected-(IC1-PC0(ADC0)-Pad23)") (class "Default")
      (node (ref "IC1") (pin "23") (pinfunction "PC0(ADC0)_23") (pintype "bidirectional"))
    )
    (net (code "80") (name "unconnected-(IC1-PD2(INT0)-Pad4)") (class "Default")
      (node (ref "IC1") (pin "4") (pinfunction "PD2(INT0)_4") (pintype "bidirectional"))
    )
    (net (code "81") (name "unconnected-(IC1-PD3(INT1)-Pad5)") (class "Default")
      (node (ref "IC1") (pin "5") (pinfunction "PD3(INT1)_5") (pintype "bidirectional"))
    )
    (net (code "82") (name "unconnected-(IC1-PD4(XCK{slash}T0)-Pad6)") (class "Default")
      (node (ref "IC1") (pin "6") (pinfunction "PD4(XCK/T0)_6") (pintype "bidirectional"))
    )
    (net (code "83") (name "unconnected-(SV2-Pad2)") (class "Default")
      (node (ref "SV2") (pin "2") (pinfunction "2_2") (pintype "passive"))
    )
    (net (code "84") (name "unconnected-(SV2-Pad12)") (class "Default")
      (node (ref "SV2") (pin "12") (pinfunction "12_12") (pintype "passive"))
    )
    (net (code "85") (name "unconnected-(SV2-Pad13)") (class "Default")
      (node (ref "SV2") (pin "13") (pinfunction "13_13") (pintype "passive"))
    )
    (net (code "86") (name "unconnected-(SV2-Pad14)") (class "Default")
      (node (ref "SV2") (pin "14") (pinfunction "14_14") (pintype "passive"))
    )
    (net (code "87") (name "unconnected-(SV2-Pad15)") (class "Default")
      (node (ref "SV2") (pin "15") (pinfunction "15_15") (pintype "passive"))
    )
    (net (code "88") (name "unconnected-(SV2-Pad16)") (class "Default")
      (node (ref "SV2") (pin "16") (pinfunction "16_16") (pintype "passive"))
    )
    (net (code "89") (name "unconnected-(U2-CBUS2-Pad13)") (class "Default")
      (node (ref "U2") (pin "13") (pinfunction "CBUS2_13") (pintype "bidirectional"))
    )
    (net (code "90") (name "unconnected-(U2-CBUS3-Pad14)") (class "Default")
      (node (ref "U2") (pin "14") (pinfunction "CBUS3_14") (pintype "bidirectional"))
    )
    (net (code "91") (name "unconnected-(U2-CBUS4-Pad12)") (class "Default")
      (node (ref "U2") (pin "12") (pinfunction "CBUS4_12") (pintype "bidirectional"))
    )
    (net (code "92") (name "unconnected-(U2-CTS#-Pad11)") (class "Default")
      (node (ref "U2") (pin "11") (pinfunction "CTS#_11") (pintype "input"))
    )
    (net (code "93") (name "unconnected-(U2-DCD#-Pad10)") (class "Default")
      (node (ref "U2") (pin "10") (pinfunction "DCD#_10") (pintype "input"))
    )
    (net (code "94") (name "unconnected-(U2-DSR#-Pad9)") (class "Default")
      (node (ref "U2") (pin "9") (pinfunction "DSR#_9") (pintype "input"))
    )
    (net (code "95") (name "unconnected-(U2-DTR#-Pad2)") (class "Default")
      (node (ref "U2") (pin "2") (pinfunction "DTR#_2") (pintype "output"))
    )
    (net (code "96") (name "unconnected-(U2-OSCI-Pad27)") (class "Default")
      (node (ref "U2") (pin "27") (pinfunction "OSCI_27") (pintype "input"))
    )
    (net (code "97") (name "unconnected-(U2-OSCO-Pad28)") (class "Default")
      (node (ref "U2") (pin "28") (pinfunction "OSCO_28") (pintype "output"))
    )
    (net (code "98") (name "unconnected-(U2-RI#-Pad6)") (class "Default")
      (node (ref "U2") (pin "6") (pinfunction "RI#_6") (pintype "input"))
    )
    (net (code "99") (name "unconnected-(U2-RTS#-Pad3)") (class "Default")
      (node (ref "U2") (pin "3") (pinfunction "RTS#_3") (pintype "output"))
    )
  )
)
